# TL074.net
KiCad netlist of a schematic drawn in Altium Designer
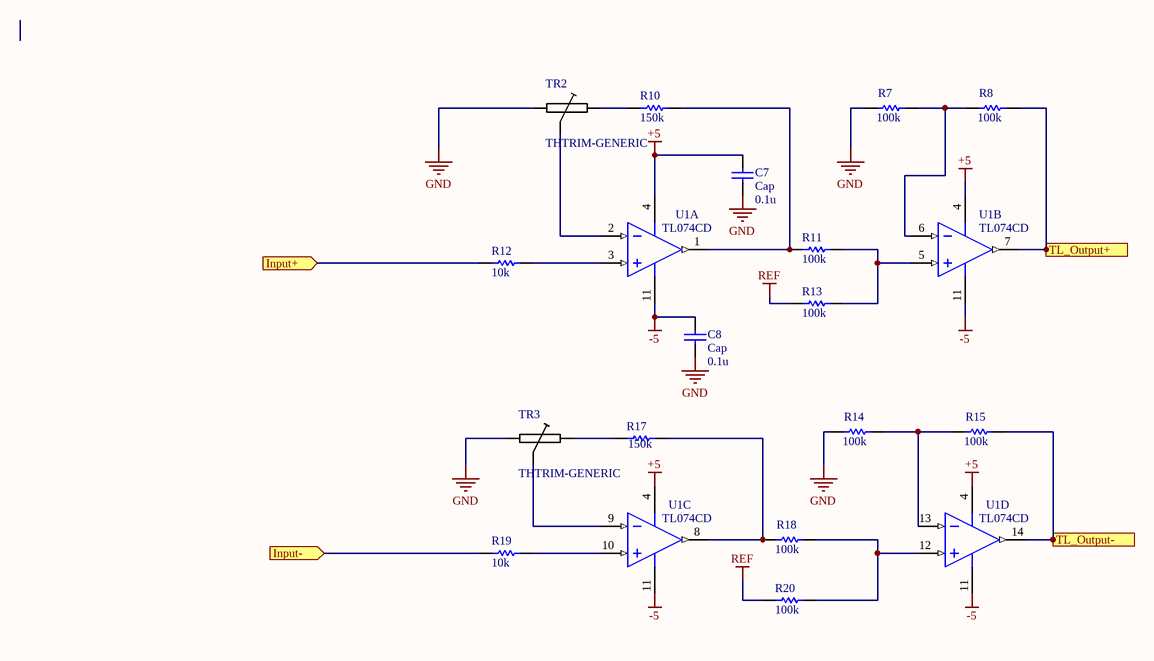
[diagram p0: TL074.SchDoc]

(export (version "E")
  (design (tool "Eeschema 10.0.6"))
  (components
    (comp (ref "C7")
      (value "Cap")
      (footprint "C1206")
      (description "Capacitor")
      (fields (field (name "ALTIUM_VALUE") "0.1u") (field (name "PUBLISHER") "Altium Limited"))
      (libsource (lib "Miscellaneous Devices") (part "Cap"))
    )
    (comp (ref "C8")
      (value "Cap")
      (footprint "C1206")
      (description "Capacitor")
      (fields (field (name "ALTIUM_VALUE") "0.1u") (field (name "PUBLISHER") "Altium Limited"))
      (libsource (lib "Miscellaneous Devices") (part "Cap"))
    )
    (comp (ref "R7")
      (value "100k")
      (footprint "RESC3216X89X51LL25T25")
      (fields (field (name "PART NUMBER") "WSLP1206R0500FEA") (field (name "MANUFACTURER") "Vishay Dale"))
      (libsource (lib "Altium Content Vault") (part "RES"))
    )
    (comp (ref "R8")
      (value "100k")
      (footprint "RESC3216X89X51LL25T25")
      (fields (field (name "PART NUMBER") "WSLP1206R0500FEA") (field (name "MANUFACTURER") "Vishay Dale"))
      (libsource (lib "Altium Content Vault") (part "RES"))
    )
    (comp (ref "R10")
      (value "150k")
      (footprint "RESC3216X89X51LL25T25")
      (fields (field (name "PART NUMBER") "WSLP1206R0500FEA") (field (name "MANUFACTURER") "Vishay Dale"))
      (libsource (lib "Altium Content Vault") (part "RES"))
    )
    (comp (ref "R11")
      (value "100k")
      (footprint "RESC3216X89X51LL25T25")
      (fields (field (name "PART NUMBER") "WSLP1206R0500FEA") (field (name "MANUFACTURER") "Vishay Dale"))
      (libsource (lib "Altium Content Vault") (part "RES"))
    )
    (comp (ref "R12")
      (value "10k")
      (footprint "RESC3216X89X51LL25T25")
      (fields (field (name "PART NUMBER") "WSLP1206R0500FEA") (field (name "MANUFACTURER") "Vishay Dale"))
      (libsource (lib "Altium Content Vault") (part "RES"))
    )
    (comp (ref "R13")
      (value "100k")
      (footprint "RESC3216X89X51LL25T25")
      (fields (field (name "PART NUMBER") "WSLP1206R0500FEA") (field (name "MANUFACTURER") "Vishay Dale"))
      (libsource (lib "Altium Content Vault") (part "RES"))
    )
    (comp (ref "R14")
      (value "100k")
      (footprint "RESC3216X89X51LL25T25")
      (fields (field (name "PART NUMBER") "WSLP1206R0500FEA") (field (name "MANUFACTURER") "Vishay Dale"))
      (libsource (lib "Altium Content Vault") (part "RES"))
    )
    (comp (ref "R15")
      (value "100k")
      (footprint "RESC3216X89X51LL25T25")
      (fields (field (name "PART NUMBER") "WSLP1206R0500FEA") (field (name "MANUFACTURER") "Vishay Dale"))
      (libsource (lib "Altium Content Vault") (part "RES"))
    )
    (comp (ref "R17")
      (value "150k")
      (footprint "RESC3216X89X51LL25T25")
      (fields (field (name "PART NUMBER") "WSLP1206R0500FEA") (field (name "MANUFACTURER") "Vishay Dale"))
      (libsource (lib "Altium Content Vault") (part "RES"))
    )
    (comp (ref "R18")
      (value "100k")
      (footprint "RESC3216X89X51LL25T25")
      (fields (field (name "PART NUMBER") "WSLP1206R0500FEA") (field (name "MANUFACTURER") "Vishay Dale"))
      (libsource (lib "Altium Content Vault") (part "RES"))
    )
    (comp (ref "R19")
      (value "10k")
      (footprint "RESC3216X89X51LL25T25")
      (fields (field (name "PART NUMBER") "WSLP1206R0500FEA") (field (name "MANUFACTURER") "Vishay Dale"))
      (libsource (lib "Altium Content Vault") (part "RES"))
    )
    (comp (ref "R20")
      (value "100k")
      (footprint "RESC3216X89X51LL25T25")
      (fields (field (name "PART NUMBER") "WSLP1206R0500FEA") (field (name "MANUFACTURER") "Vishay Dale"))
      (libsource (lib "Altium Content Vault") (part "RES"))
    )
    (comp (ref "TR2")
      (value "THTRIM-GENERIC")
      (footprint "TRIMMER-MT")
      (description "TRIMMABLE RESISTOR")
      (libsource (lib "vh_altium_library") (part "THTRIM-GENERIC"))
    )
    (comp (ref "TR3")
      (value "THTRIM-GENERIC")
      (footprint "TRIMMER-MT")
      (description "TRIMMABLE RESISTOR")
      (libsource (lib "vh_altium_library") (part "THTRIM-GENERIC"))
    )
    (comp (ref "U1")
      (value "TL074CD")
      (footprint "D0014A_M")
      (fields (field (name "MANUFACTURER") "Texas Instruments"))
      (libsource (lib "Altium Content Vault") (part "TI-TLXX4X_MC3403-X14"))
    )
  )
  (nets
    (net (code "1") (name "+5") (class "Default")
      (node (ref "C7") (pin "1") (pinfunction "1_1") (pintype "passive"))
      (node (ref "U1") (pin "4") (pinfunction "VCC+_4") (pintype "power_in"))
    )
    (net (code "2") (name "-5") (class "Default")
      (node (ref "C8") (pin "1") (pinfunction "1_1") (pintype "passive"))
      (node (ref "U1") (pin "11") (pinfunction "VCC-_11") (pintype "power_in"))
    )
    (net (code "3") (name "/Input+") (class "Default")
      (node (ref "R12") (pin "2") (pinfunction "2_2") (pintype "passive"))
    )
    (net (code "4") (name "/Input-") (class "Default")
      (node (ref "R19") (pin "2") (pinfunction "2_2") (pintype "passive"))
    )
    (net (code "5") (name "/TL_Output+") (class "Default")
      (node (ref "R8") (pin "1") (pinfunction "1_1") (pintype "passive"))
      (node (ref "U1") (pin "7") (pinfunction "OUT2_7") (pintype "output"))
    )
    (net (code "6") (name "/TL_Output-") (class "Default")
      (node (ref "R15") (pin "1") (pinfunction "1_1") (pintype "passive"))
      (node (ref "U1") (pin "14") (pinfunction "OUT4_14") (pintype "output"))
    )
    (net (code "7") (name "GND") (class "Default")
      (node (ref "C7") (pin "2") (pinfunction "2_2") (pintype "passive"))
      (node (ref "C8") (pin "2") (pinfunction "2_2") (pintype "passive"))
      (node (ref "R14") (pin "2") (pinfunction "2_2") (pintype "passive"))
      (node (ref "R7") (pin "2") (pinfunction "2_2") (pintype "passive"))
      (node (ref "TR2") (pin "1") (pinfunction "1_1") (pintype "passive"))
      (node (ref "TR3") (pin "1") (pinfunction "1_1") (pintype "passive"))
    )
    (net (code "8") (name "Net-(R10-Pad2)") (class "Default")
      (node (ref "R10") (pin "2") (pinfunction "2_2") (pintype "passive"))
      (node (ref "TR2") (pin "2") (pinfunction "2_2") (pintype "passive"))
    )
    (net (code "9") (name "Net-(R17-Pad2)") (class "Default")
      (node (ref "R17") (pin "2") (pinfunction "2_2") (pintype "passive"))
      (node (ref "TR3") (pin "2") (pinfunction "2_2") (pintype "passive"))
    )
    (net (code "10") (name "Net-(U1A-IN1+)") (class "Default")
      (node (ref "R12") (pin "1") (pinfunction "1_1") (pintype "passive"))
      (node (ref "U1") (pin "3") (pinfunction "IN1+_3") (pintype "input"))
    )
    (net (code "11") (name "Net-(U1A-IN1-)") (class "Default")
      (node (ref "TR2") (pin "W") (pinfunction "W_W") (pintype "passive"))
      (node (ref "U1") (pin "2") (pinfunction "IN1-_2") (pintype "input"))
    )
    (net (code "12") (name "Net-(U1A-OUT1)") (class "Default")
      (node (ref "R10") (pin "1") (pinfunction "1_1") (pintype "passive"))
      (node (ref "R11") (pin "2") (pinfunction "2_2") (pintype "passive"))
      (node (ref "U1") (pin "1") (pinfunction "OUT1_1") (pintype "output"))
    )
    (net (code "13") (name "Net-(U1B-IN2+)") (class "Default")
      (node (ref "R11") (pin "1") (pinfunction "1_1") (pintype "passive"))
      (node (ref "R13") (pin "1") (pinfunction "1_1") (pintype "passive"))
      (node (ref "U1") (pin "5") (pinfunction "IN2+_5") (pintype "input"))
    )
    (net (code "14") (name "Net-(U1B-IN2-)") (class "Default")
      (node (ref "R7") (pin "1") (pinfunction "1_1") (pintype "passive"))
      (node (ref "R8") (pin "2") (pinfunction "2_2") (pintype "passive"))
      (node (ref "U1") (pin "6") (pinfunction "IN2-_6") (pintype "input"))
    )
    (net (code "15") (name "Net-(U1C-IN3+)") (class "Default")
      (node (ref "R19") (pin "1") (pinfunction "1_1") (pintype "passive"))
      (node (ref "U1") (pin "10") (pinfunction "IN3+_10") (pintype "input"))
    )
    (net (code "16") (name "Net-(U1C-IN3-)") (class "Default")
      (node (ref "TR3") (pin "W") (pinfunction "W_W") (pintype "passive"))
      (node (ref "U1") (pin "9") (pinfunction "IN3-_9") (pintype "input"))
    )
    (net (code "17") (name "Net-(U1C-OUT3)") (class "Default")
      (node (ref "R17") (pin "1") (pinfunction "1_1") (pintype "passive"))
      (node (ref "R18") (pin "2") (pinfunction "2_2") (pintype "passive"))
      (node (ref "U1") (pin "8") (pinfunction "OUT3_8") (pintype "output"))
    )
    (net (code "18") (name "Net-(U1D-IN4+)") (class "Default")
      (node (ref "R18") (pin "1") (pinfunction "1_1") (pintype "passive"))
      (node (ref "R20") (pin "1") (pinfunction "1_1") (pintype "passive"))
      (node (ref "U1") (pin "12") (pinfunction "IN4+_12") (pintype "input"))
    )
    (net (code "19") (name "Net-(U1D-IN4-)") (class "Default")
      (node (ref "R14") (pin "1") (pinfunction "1_1") (pintype "passive"))
      (node (ref "R15") (pin "2") (pinfunction "2_2") (pintype "passive"))
      (node (ref "U1") (pin "13") (pinfunction "IN4-_13") (pintype "input"))
    )
    (net (code "20") (name "REF") (class "Default")
      (node (ref "R13") (pin "2") (pinfunction "2_2") (pintype "passive"))
      (node (ref "R20") (pin "2") (pinfunction "2_2") (pintype "passive"))
    )
  )
)
